# Sheet1.net
KiCad netlist of a schematic drawn in Altium Designer
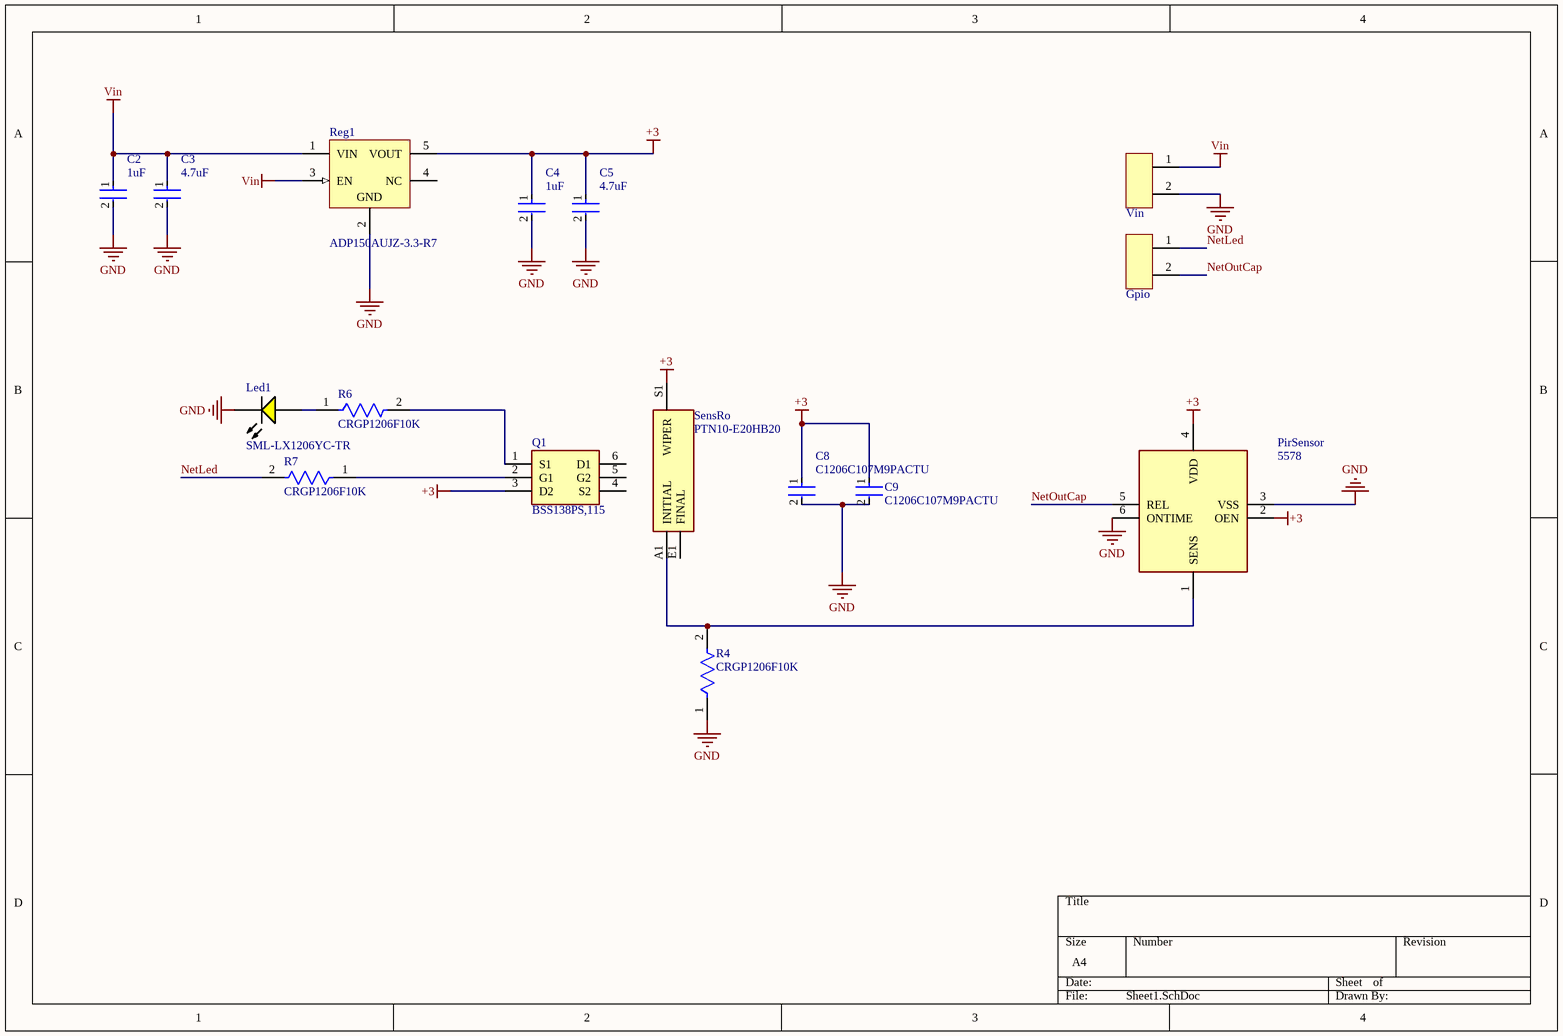
[diagram p0: Sheet1.SchDoc]

(export (version "E")
  (design (tool "Eeschema 10.0.6"))
  (components
    (comp (ref "C2")
      (value "1uF")
      (footprint "FP-C1206C-EH-MFG")
      (description "CAP CER 100UF 6.3V X5R 1206")
      (fields (field (name "TOLERANCE") "2%") (field (name "VOLTAGE") "6.3V"))
      (libsource (lib "Altium Content Vault") (part "02cd4be3c70576c341d710602a673aa"))
    )
    (comp (ref "C3")
      (value "4.7uF")
      (footprint "FP-C1206C-EH-MFG")
      (description "CAP CER 100UF 6.3V X5R 1206")
      (fields (field (name "TOLERANCE") "2%") (field (name "VOLTAGE") "6.3V"))
      (libsource (lib "Altium Content Vault") (part "02cd4be3c70576c341d710602a673aa"))
    )
    (comp (ref "C4")
      (value "1uF")
      (footprint "FP-C1206C-EH-MFG")
      (description "CAP CER 100UF 6.3V X5R 1206")
      (fields (field (name "TOLERANCE") "2%") (field (name "VOLTAGE") "6.3V"))
      (libsource (lib "Altium Content Vault") (part "02cd4be3c70576c341d710602a673aa"))
    )
    (comp (ref "C5")
      (value "4.7uF")
      (footprint "FP-C1206C-EH-MFG")
      (description "CAP CER 100UF 6.3V X5R 1206")
      (fields (field (name "TOLERANCE") "2%") (field (name "VOLTAGE") "6.3V"))
      (libsource (lib "Altium Content Vault") (part "02cd4be3c70576c341d710602a673aa"))
    )
    (comp (ref "C8")
      (value "C1206C107M9PACTU")
      (footprint "FP-C1206C-EH-MFG")
      (description "CAP CER 100UF 6.3V X5R 1206")
      (fields (field (name "TOLERANCE") "2%") (field (name "VOLTAGE") "6.3V"))
      (libsource (lib "Altium Content Vault") (part "02cd4be3c70576c341d710602a673aa"))
    )
    (comp (ref "C9")
      (value "C1206C107M9PACTU")
      (footprint "FP-C1206C-EH-MFG")
      (description "CAP CER 100UF 6.3V X5R 1206")
      (fields (field (name "TOLERANCE") "2%") (field (name "VOLTAGE") "6.3V"))
      (libsource (lib "Altium Content Vault") (part "02cd4be3c70576c341d710602a673aa"))
    )
    (comp (ref "Gpio")
      (value "~")
      (footprint "TS-75x70")
      (description "Fixed Terminal Blocks PT 1.5/2-3.5H 2POS HRZ 3.5mm SCREW")
      (fields
        (field (name "MANUFACTURER") "Phoenix Contact")
        (field (name "MANUFACTURER PART NUMBER") "1984617")
      )
      (libsource (lib "AltiumCAOQ2_2023") (part "Connector-2"))
    )
    (comp (ref "Led1")
      (value "SML-LX1206YC-TR")
      (footprint "LUMX-SML-LX1206YC-TR_V")
      (description "Yellow LED, Water Clear Len, 585 nm, 2.1 V, -40 to 85 degC, 2-Pin SMD, RoHS, Tape and Reel")
      (fields (field (name "MANUFACTURER") "Lumex"))
      (libsource (lib "Altium Content Vault") (part "LED-YELLOW-AK-2"))
    )
    (comp (ref "PirSensor")
      (value "5578")
      (footprint "SamacSys:5578")
      (description "Integrated Circuit")
      (fields (field (name "MOUSER PART NUMBER") "485-5578"))
      (libsource (lib "*") (part "5578"))
    )
    (comp (ref "Q1")
      (value "BSS138PS,115")
      (footprint "SamacSys:SOT65P210X110-6N")
      (description "MOSFET (N-Channel)")
      (fields (field (name "MOUSER PART NUMBER") "771-BSS138PS115"))
      (libsource (lib "*") (part "BSS138PS,115"))
    )
    (comp (ref "R4")
      (value "CRGP1206F10K")
      (footprint "FP-CRGP1206-IPC_C")
      (description "CRGP 1206 10K 1%")
      (fields
        (field (name "OCTOPART") "https://octopart.com/crgp1206f10k-te+connectivity-91018843")
        (field (name "TOLERANCE") "0.01")
      )
      (libsource (lib "Altium Content Vault") (part "1029c3af85768c4190bb7ad29bc67b5"))
    )
    (comp (ref "R6")
      (value "CRGP1206F10K")
      (footprint "FP-CRGP1206-IPC_C")
      (description "CRGP 1206 10K 1%")
      (fields
        (field (name "OCTOPART") "https://octopart.com/crgp1206f10k-te+connectivity-91018843")
        (field (name "TOLERANCE") "0.01")
      )
      (libsource (lib "Altium Content Vault") (part "1029c3af85768c4190bb7ad29bc67b5"))
    )
    (comp (ref "R7")
      (value "CRGP1206F10K")
      (footprint "FP-CRGP1206-IPC_C")
      (description "CRGP 1206 10K 1%")
      (fields
        (field (name "OCTOPART") "https://octopart.com/crgp1206f10k-te+connectivity-91018843")
        (field (name "TOLERANCE") "0.01")
      )
      (libsource (lib "Altium Content Vault") (part "1029c3af85768c4190bb7ad29bc67b5"))
    )
    (comp (ref "Reg1")
      (value "ADP150AUJZ-3.3-R7")
      (footprint "ADI-UJ-5_M")
      (fields (field (name "MANUFACTURER") "Analog Devices"))
      (libsource (lib "Altium Content Vault") (part "ADI-ADP1XX-UJ-5"))
    )
    (comp (ref "SensRo")
      (value "PTN10-E20HB20")
      (footprint "SamacSys:PTN10E20HB20")
      (description "Variable Resistor")
      (fields (field (name "MOUSER PART NUMBER") "179-PTN10-E20HB20"))
      (libsource (lib "*") (part "PTN10-E20HB20"))
    )
    (comp (ref "Vin")
      (value "~")
      (footprint "TS-75x70")
      (description "Fixed Terminal Blocks PT 1.5/2-3.5H 2POS HRZ 3.5mm SCREW")
      (fields
        (field (name "MANUFACTURER") "Phoenix Contact")
        (field (name "MANUFACTURER PART NUMBER") "1984617")
      )
      (libsource (lib "AltiumCAOQ2_2023") (part "Connector-2"))
    )
  )
  (nets
    (net (code "1") (name "+3") (class "Default")
      (node (ref "C4") (pin "1") (pinfunction "1_1") (pintype "passive"))
      (node (ref "C5") (pin "1") (pinfunction "1_1") (pintype "passive"))
      (node (ref "C8") (pin "1") (pinfunction "1_1") (pintype "passive"))
      (node (ref "C9") (pin "1") (pinfunction "1_1") (pintype "passive"))
      (node (ref "PirSensor") (pin "2") (pinfunction "OEN_2") (pintype "passive"))
      (node (ref "PirSensor") (pin "4") (pinfunction "VDD_4") (pintype "passive"))
      (node (ref "Q1") (pin "3") (pinfunction "D2_3") (pintype "passive"))
      (node (ref "Reg1") (pin "5") (pinfunction "VOUT_5") (pintype "power_in"))
      (node (ref "SensRo") (pin "S1") (pinfunction "WIPER_S1") (pintype "passive"))
    )
    (net (code "2") (name "/NetLed") (class "Default")
      (node (ref "Gpio") (pin "1") (pintype "passive"))
      (node (ref "R7") (pin "2") (pinfunction "2_2") (pintype "passive"))
    )
    (net (code "3") (name "/NetOutCap") (class "Default")
      (node (ref "Gpio") (pin "2") (pintype "passive"))
      (node (ref "PirSensor") (pin "5") (pinfunction "REL_5") (pintype "passive"))
    )
    (net (code "4") (name "GND") (class "Default")
      (node (ref "C2") (pin "2") (pinfunction "2_2") (pintype "passive"))
      (node (ref "C3") (pin "2") (pinfunction "2_2") (pintype "passive"))
      (node (ref "C4") (pin "2") (pinfunction "2_2") (pintype "passive"))
      (node (ref "C5") (pin "2") (pinfunction "2_2") (pintype "passive"))
      (node (ref "C8") (pin "2") (pinfunction "2_2") (pintype "passive"))
      (node (ref "C9") (pin "2") (pinfunction "2_2") (pintype "passive"))
      (node (ref "Led1") (pin "2") (pinfunction "K_2") (pintype "passive"))
      (node (ref "PirSensor") (pin "3") (pinfunction "VSS_3") (pintype "passive"))
      (node (ref "PirSensor") (pin "6") (pinfunction "ONTIME_6") (pintype "passive"))
      (node (ref "R4") (pin "1") (pinfunction "1_1") (pintype "passive"))
      (node (ref "Reg1") (pin "2") (pinfunction "GND_2") (pintype "power_in"))
      (node (ref "Vin") (pin "2") (pintype "passive"))
    )
    (net (code "5") (name "Net-(Led1-A)") (class "Default")
      (node (ref "Led1") (pin "1") (pinfunction "A_1") (pintype "passive"))
      (node (ref "R6") (pin "1") (pinfunction "1_1") (pintype "passive"))
    )
    (net (code "6") (name "Net-(PirSensor-SENS)") (class "Default")
      (node (ref "PirSensor") (pin "1") (pinfunction "SENS_1") (pintype "passive"))
      (node (ref "R4") (pin "2") (pinfunction "2_2") (pintype "passive"))
      (node (ref "SensRo") (pin "A1") (pinfunction "INITIAL_A1") (pintype "passive"))
    )
    (net (code "7") (name "Net-(Q1-G1)") (class "Default")
      (node (ref "Q1") (pin "2") (pinfunction "G1_2") (pintype "passive"))
      (node (ref "R7") (pin "1") (pinfunction "1_1") (pintype "passive"))
    )
    (net (code "8") (name "Net-(Q1-S1)") (class "Default")
      (node (ref "Q1") (pin "1") (pinfunction "S1_1") (pintype "passive"))
      (node (ref "R6") (pin "2") (pinfunction "2_2") (pintype "passive"))
    )
    (net (code "9") (name "Vin") (class "Default")
      (node (ref "C2") (pin "1") (pinfunction "1_1") (pintype "passive"))
      (node (ref "C3") (pin "1") (pinfunction "1_1") (pintype "passive"))
      (node (ref "Reg1") (pin "1") (pinfunction "VIN_1") (pintype "power_in"))
      (node (ref "Reg1") (pin "3") (pinfunction "EN_3") (pintype "input"))
      (node (ref "Vin") (pin "1") (pintype "passive"))
    )
    (net (code "10") (name "unconnected-(Q1-D1-Pad6)") (class "Default")
      (node (ref "Q1") (pin "6") (pinfunction "D1_6") (pintype "passive"))
    )
    (net (code "11") (name "unconnected-(Q1-G2-Pad5)") (class "Default")
      (node (ref "Q1") (pin "5") (pinfunction "G2_5") (pintype "passive"))
    )
    (net (code "12") (name "unconnected-(Q1-S2-Pad4)") (class "Default")
      (node (ref "Q1") (pin "4") (pinfunction "S2_4") (pintype "passive"))
    )
    (net (code "13") (name "unconnected-(Reg1-NC-Pad4)") (class "Default")
      (node (ref "Reg1") (pin "4") (pinfunction "NC_4") (pintype "passive"))
    )
    (net (code "14") (name "unconnected-(SensRo-FINAL-PadE1)") (class "Default")
      (node (ref "SensRo") (pin "E1") (pinfunction "FINAL_E1") (pintype "passive"))
    )
  )
)
